# ButtonInputBoard.net
KiCad netlist of a schematic drawn in Altium Designer
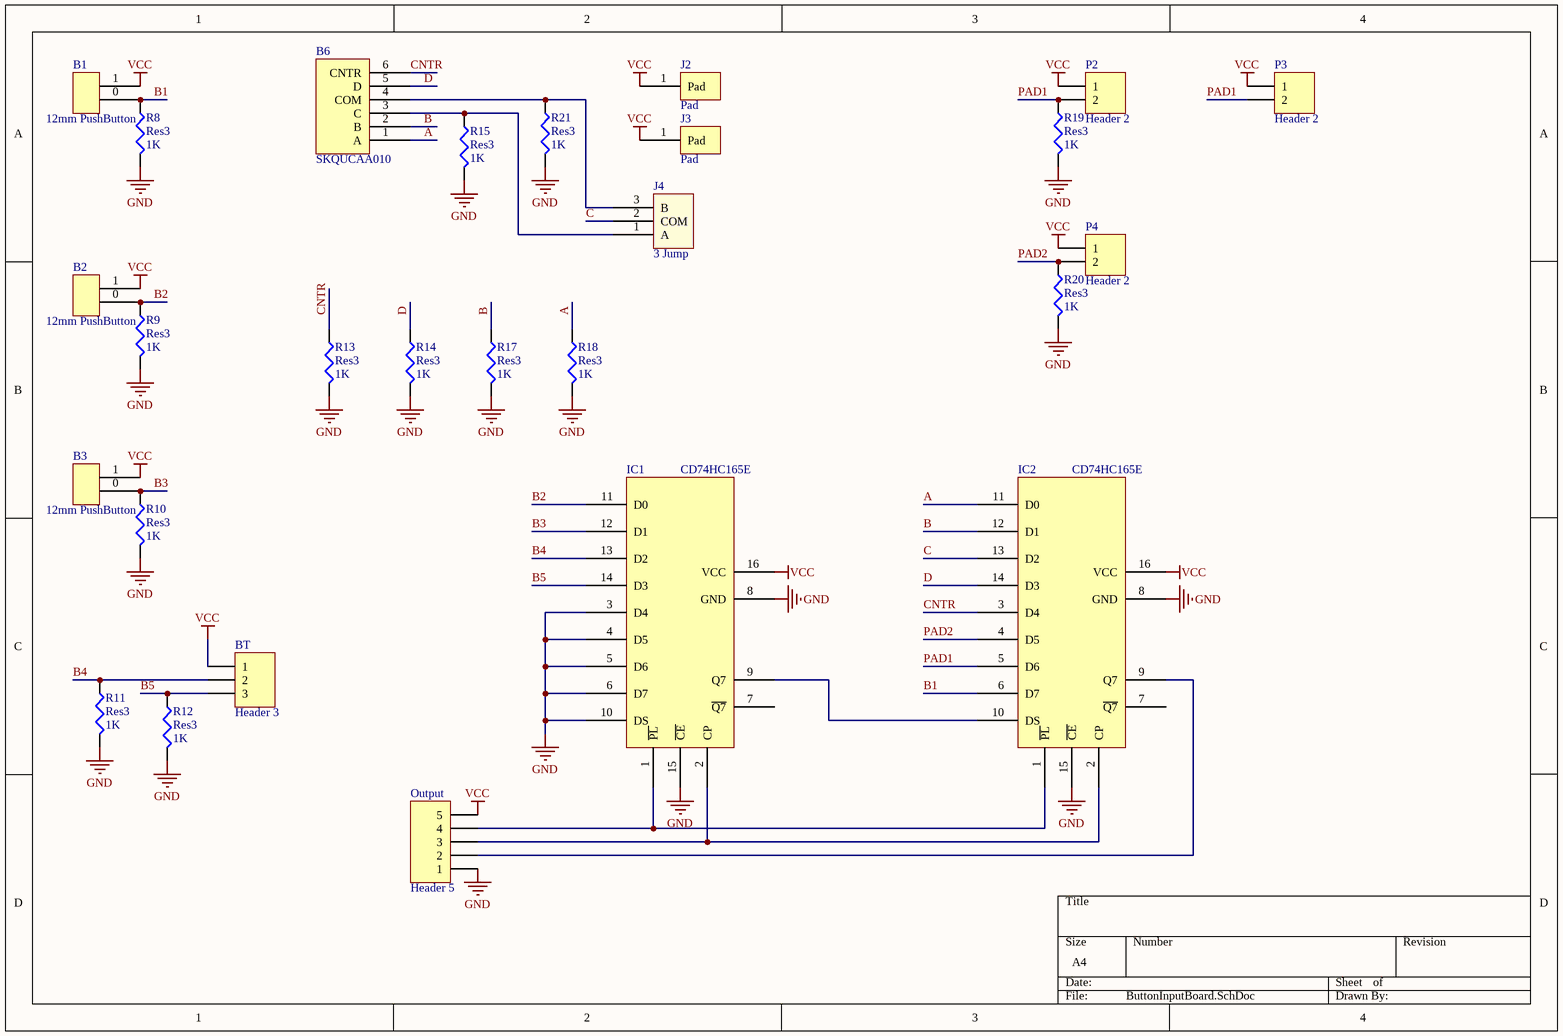
[diagram p0: ButtonInputBoard.SchDoc]

(export (version "E")
  (design (tool "Eeschema 10.0.6"))
  (components
    (comp (ref "B1")
      (value "12mm PushButton")
      (footprint "12mm PushButton")
      (libsource (lib "WheelLib") (part "12mm PushButton"))
    )
    (comp (ref "B2")
      (value "12mm PushButton")
      (footprint "12mm PushButton")
      (libsource (lib "WheelLib") (part "12mm PushButton"))
    )
    (comp (ref "B3")
      (value "12mm PushButton")
      (footprint "12mm PushButton")
      (libsource (lib "WheelLib") (part "12mm PushButton"))
    )
    (comp (ref "B6")
      (value "SKQUCAA010")
      (footprint "SKQUCAA010")
      (libsource (lib "WheelLib") (part "SKQUCAA010"))
    )
    (comp (ref "BT")
      (value "Header 3")
      (footprint "HDR1X3")
      (description "Header, 3-Pin")
      (fields (field (name "PUBLISHER") "Altium Limited"))
      (libsource (lib "Miscellaneous Connectors") (part "Header 3"))
    )
    (comp (ref "IC1")
      (value "CD74HC165E")
      (footprint "SD74HC165E")
      (description "8-Bit Shift Register")
      (libsource (lib "WheelLib") (part "CD74HC165E"))
    )
    (comp (ref "IC2")
      (value "CD74HC165E")
      (footprint "SD74HC165E")
      (description "8-Bit Shift Register")
      (libsource (lib "WheelLib") (part "CD74HC165E"))
    )
    (comp (ref "J2") (value "Pad") (footprint "Pad") (libsource (lib "WheelLib") (part "Pad")))
    (comp (ref "J3") (value "Pad") (footprint "Pad") (libsource (lib "WheelLib") (part "Pad")))
    (comp (ref "J4") (value "3 Jump") (footprint "3 Jump") (libsource (lib "WheelLib") (part "3 Jump")))
    (comp (ref "Output")
      (value "Header 5")
      (footprint "HDR1X5")
      (description "Header, 5-Pin")
      (fields (field (name "PUBLISHER") "Altium Limited"))
      (libsource (lib "Miscellaneous Connectors") (part "Header 5"))
    )
    (comp (ref "P2")
      (value "Header 2")
      (footprint "HDR1X2")
      (description "Header, 2-Pin")
      (fields (field (name "PUBLISHER") "Altium Limited"))
      (libsource (lib "Miscellaneous Connectors") (part "Header 2"))
    )
    (comp (ref "P3")
      (value "Header 2")
      (footprint "HDR1X2")
      (description "Header, 2-Pin")
      (fields (field (name "PUBLISHER") "Altium Limited"))
      (libsource (lib "Miscellaneous Connectors") (part "Header 2"))
    )
    (comp (ref "P4")
      (value "Header 2")
      (footprint "HDR1X2")
      (description "Header, 2-Pin")
      (fields (field (name "PUBLISHER") "Altium Limited"))
      (libsource (lib "Miscellaneous Connectors") (part "Header 2"))
    )
    (comp (ref "R8")
      (value "Res3")
      (footprint "J1-0603")
      (description "Resistor")
      (fields (field (name "ALTIUM_VALUE") "1K") (field (name "PUBLISHER") "Altium Limited"))
      (libsource (lib "Miscellaneous Devices") (part "Res3"))
    )
    (comp (ref "R9")
      (value "Res3")
      (footprint "J1-0603")
      (description "Resistor")
      (fields (field (name "ALTIUM_VALUE") "1K") (field (name "PUBLISHER") "Altium Limited"))
      (libsource (lib "Miscellaneous Devices") (part "Res3"))
    )
    (comp (ref "R10")
      (value "Res3")
      (footprint "J1-0603")
      (description "Resistor")
      (fields (field (name "ALTIUM_VALUE") "1K") (field (name "PUBLISHER") "Altium Limited"))
      (libsource (lib "Miscellaneous Devices") (part "Res3"))
    )
    (comp (ref "R11")
      (value "Res3")
      (footprint "J1-0603")
      (description "Resistor")
      (fields (field (name "ALTIUM_VALUE") "1K") (field (name "PUBLISHER") "Altium Limited"))
      (libsource (lib "Miscellaneous Devices") (part "Res3"))
    )
    (comp (ref "R12")
      (value "Res3")
      (footprint "J1-0603")
      (description "Resistor")
      (fields (field (name "ALTIUM_VALUE") "1K") (field (name "PUBLISHER") "Altium Limited"))
      (libsource (lib "Miscellaneous Devices") (part "Res3"))
    )
    (comp (ref "R13")
      (value "Res3")
      (footprint "J1-0603")
      (description "Resistor")
      (fields (field (name "ALTIUM_VALUE") "1K") (field (name "PUBLISHER") "Altium Limited"))
      (libsource (lib "Miscellaneous Devices") (part "Res3"))
    )
    (comp (ref "R14")
      (value "Res3")
      (footprint "J1-0603")
      (description "Resistor")
      (fields (field (name "ALTIUM_VALUE") "1K") (field (name "PUBLISHER") "Altium Limited"))
      (libsource (lib "Miscellaneous Devices") (part "Res3"))
    )
    (comp (ref "R15")
      (value "Res3")
      (footprint "J1-0603")
      (description "Resistor")
      (fields (field (name "ALTIUM_VALUE") "1K") (field (name "PUBLISHER") "Altium Limited"))
      (libsource (lib "Miscellaneous Devices") (part "Res3"))
    )
    (comp (ref "R17")
      (value "Res3")
      (footprint "J1-0603")
      (description "Resistor")
      (fields (field (name "ALTIUM_VALUE") "1K") (field (name "PUBLISHER") "Altium Limited"))
      (libsource (lib "Miscellaneous Devices") (part "Res3"))
    )
    (comp (ref "R18")
      (value "Res3")
      (footprint "J1-0603")
      (description "Resistor")
      (fields (field (name "ALTIUM_VALUE") "1K") (field (name "PUBLISHER") "Altium Limited"))
      (libsource (lib "Miscellaneous Devices") (part "Res3"))
    )
    (comp (ref "R19")
      (value "Res3")
      (footprint "J1-0603")
      (description "Resistor")
      (fields (field (name "ALTIUM_VALUE") "1K") (field (name "PUBLISHER") "Altium Limited"))
      (libsource (lib "Miscellaneous Devices") (part "Res3"))
    )
    (comp (ref "R20")
      (value "Res3")
      (footprint "J1-0603")
      (description "Resistor")
      (fields (field (name "ALTIUM_VALUE") "1K") (field (name "PUBLISHER") "Altium Limited"))
      (libsource (lib "Miscellaneous Devices") (part "Res3"))
    )
    (comp (ref "R21")
      (value "Res3")
      (footprint "J1-0603")
      (description "Resistor")
      (fields (field (name "ALTIUM_VALUE") "1K") (field (name "PUBLISHER") "Altium Limited"))
      (libsource (lib "Miscellaneous Devices") (part "Res3"))
    )
  )
  (nets
    (net (code "1") (name "/A") (class "Default")
      (node (ref "B6") (pin "1") (pinfunction "A_1") (pintype "passive"))
      (node (ref "IC2") (pin "11") (pinfunction "D0_11") (pintype "passive"))
      (node (ref "R18") (pin "1") (pinfunction "1_1") (pintype "passive"))
    )
    (net (code "2") (name "/B") (class "Default")
      (node (ref "B6") (pin "2") (pinfunction "B_2") (pintype "passive"))
      (node (ref "IC2") (pin "12") (pinfunction "D1_12") (pintype "passive"))
      (node (ref "R17") (pin "1") (pinfunction "1_1") (pintype "passive"))
    )
    (net (code "3") (name "/B1") (class "Default")
      (node (ref "B1") (pin "0") (pintype "passive"))
      (node (ref "IC2") (pin "6") (pinfunction "D7_6") (pintype "passive"))
      (node (ref "R8") (pin "1") (pinfunction "1_1") (pintype "passive"))
    )
    (net (code "4") (name "/B2") (class "Default")
      (node (ref "B2") (pin "0") (pintype "passive"))
      (node (ref "IC1") (pin "11") (pinfunction "D0_11") (pintype "passive"))
      (node (ref "R9") (pin "1") (pinfunction "1_1") (pintype "passive"))
    )
    (net (code "5") (name "/B3") (class "Default")
      (node (ref "B3") (pin "0") (pintype "passive"))
      (node (ref "IC1") (pin "12") (pinfunction "D1_12") (pintype "passive"))
      (node (ref "R10") (pin "1") (pinfunction "1_1") (pintype "passive"))
    )
    (net (code "6") (name "/B4") (class "Default")
      (node (ref "BT") (pin "2") (pinfunction "2_2") (pintype "passive"))
      (node (ref "IC1") (pin "13") (pinfunction "D2_13") (pintype "passive"))
      (node (ref "R11") (pin "1") (pinfunction "1_1") (pintype "passive"))
    )
    (net (code "7") (name "/B5") (class "Default")
      (node (ref "BT") (pin "3") (pinfunction "3_3") (pintype "passive"))
      (node (ref "IC1") (pin "14") (pinfunction "D3_14") (pintype "passive"))
      (node (ref "R12") (pin "1") (pinfunction "1_1") (pintype "passive"))
    )
    (net (code "8") (name "/C") (class "Default")
      (node (ref "IC2") (pin "13") (pinfunction "D2_13") (pintype "passive"))
      (node (ref "J4") (pin "2") (pinfunction "COM_2") (pintype "passive"))
    )
    (net (code "9") (name "/CNTR") (class "Default")
      (node (ref "B6") (pin "6") (pinfunction "CNTR_6") (pintype "passive"))
      (node (ref "IC2") (pin "3") (pinfunction "D4_3") (pintype "passive"))
      (node (ref "R13") (pin "1") (pinfunction "1_1") (pintype "passive"))
    )
    (net (code "10") (name "/D") (class "Default")
      (node (ref "B6") (pin "5") (pinfunction "D_5") (pintype "passive"))
      (node (ref "IC2") (pin "14") (pinfunction "D3_14") (pintype "passive"))
      (node (ref "R14") (pin "1") (pinfunction "1_1") (pintype "passive"))
    )
    (net (code "11") (name "/PAD1") (class "Default")
      (node (ref "IC2") (pin "5") (pinfunction "D6_5") (pintype "passive"))
      (node (ref "P2") (pin "2") (pinfunction "2_2") (pintype "passive"))
      (node (ref "P3") (pin "2") (pinfunction "2_2") (pintype "passive"))
      (node (ref "R19") (pin "1") (pinfunction "1_1") (pintype "passive"))
    )
    (net (code "12") (name "/PAD2") (class "Default")
      (node (ref "IC2") (pin "4") (pinfunction "D5_4") (pintype "passive"))
      (node (ref "P4") (pin "2") (pinfunction "2_2") (pintype "passive"))
      (node (ref "R20") (pin "1") (pinfunction "1_1") (pintype "passive"))
    )
    (net (code "13") (name "GND") (class "Default")
      (node (ref "IC1") (pin "10") (pinfunction "DS_10") (pintype "passive"))
      (node (ref "IC1") (pin "15") (pinfunction "~{CE}_15") (pintype "passive"))
      (node (ref "IC1") (pin "3") (pinfunction "D4_3") (pintype "passive"))
      (node (ref "IC1") (pin "4") (pinfunction "D5_4") (pintype "passive"))
      (node (ref "IC1") (pin "5") (pinfunction "D6_5") (pintype "passive"))
      (node (ref "IC1") (pin "6") (pinfunction "D7_6") (pintype "passive"))
      (node (ref "IC1") (pin "8") (pinfunction "GND_8") (pintype "power_in"))
      (node (ref "IC2") (pin "15") (pinfunction "~{CE}_15") (pintype "passive"))
      (node (ref "IC2") (pin "8") (pinfunction "GND_8") (pintype "power_in"))
      (node (ref "Output") (pin "1") (pinfunction "1_1") (pintype "passive"))
      (node (ref "R10") (pin "2") (pinfunction "2_2") (pintype "passive"))
      (node (ref "R11") (pin "2") (pinfunction "2_2") (pintype "passive"))
      (node (ref "R12") (pin "2") (pinfunction "2_2") (pintype "passive"))
      (node (ref "R13") (pin "2") (pinfunction "2_2") (pintype "passive"))
      (node (ref "R14") (pin "2") (pinfunction "2_2") (pintype "passive"))
      (node (ref "R15") (pin "2") (pinfunction "2_2") (pintype "passive"))
      (node (ref "R17") (pin "2") (pinfunction "2_2") (pintype "passive"))
      (node (ref "R18") (pin "2") (pinfunction "2_2") (pintype "passive"))
      (node (ref "R19") (pin "2") (pinfunction "2_2") (pintype "passive"))
      (node (ref "R20") (pin "2") (pinfunction "2_2") (pintype "passive"))
      (node (ref "R21") (pin "2") (pinfunction "2_2") (pintype "passive"))
      (node (ref "R8") (pin "2") (pinfunction "2_2") (pintype "passive"))
      (node (ref "R9") (pin "2") (pinfunction "2_2") (pintype "passive"))
    )
    (net (code "14") (name "Net-(B6-C)") (class "Default")
      (node (ref "B6") (pin "3") (pinfunction "C_3") (pintype "passive"))
      (node (ref "J4") (pin "1") (pinfunction "A_1") (pintype "passive"))
      (node (ref "R15") (pin "1") (pinfunction "1_1") (pintype "passive"))
    )
    (net (code "15") (name "Net-(B6-COM)") (class "Default")
      (node (ref "B6") (pin "4") (pinfunction "COM_4") (pintype "passive"))
      (node (ref "J4") (pin "3") (pinfunction "B_3") (pintype "passive"))
      (node (ref "R21") (pin "1") (pinfunction "1_1") (pintype "passive"))
    )
    (net (code "16") (name "Net-(IC1-CP)") (class "Default")
      (node (ref "IC1") (pin "2") (pinfunction "CP_2") (pintype "passive"))
      (node (ref "IC2") (pin "2") (pinfunction "CP_2") (pintype "passive"))
      (node (ref "Output") (pin "3") (pinfunction "3_3") (pintype "passive"))
    )
    (net (code "17") (name "Net-(IC1-Q7)") (class "Default")
      (node (ref "IC1") (pin "9") (pinfunction "Q7_9") (pintype "passive"))
      (node (ref "IC2") (pin "10") (pinfunction "DS_10") (pintype "passive"))
    )
    (net (code "18") (name "Net-(IC1-~{PL})") (class "Default")
      (node (ref "IC1") (pin "1") (pinfunction "~{PL}_1") (pintype "passive"))
      (node (ref "IC2") (pin "1") (pinfunction "~{PL}_1") (pintype "passive"))
      (node (ref "Output") (pin "4") (pinfunction "4_4") (pintype "passive"))
    )
    (net (code "19") (name "Net-(IC2-Q7)") (class "Default")
      (node (ref "IC2") (pin "9") (pinfunction "Q7_9") (pintype "passive"))
      (node (ref "Output") (pin "2") (pinfunction "2_2") (pintype "passive"))
    )
    (net (code "20") (name "VCC") (class "Default")
      (node (ref "B1") (pin "1") (pintype "passive"))
      (node (ref "B2") (pin "1") (pintype "passive"))
      (node (ref "B3") (pin "1") (pintype "passive"))
      (node (ref "BT") (pin "1") (pinfunction "1_1") (pintype "passive"))
      (node (ref "IC1") (pin "16") (pinfunction "VCC_16") (pintype "power_in"))
      (node (ref "IC2") (pin "16") (pinfunction "VCC_16") (pintype "power_in"))
      (node (ref "J2") (pin "1") (pinfunction "Pad_1") (pintype "passive"))
      (node (ref "J3") (pin "1") (pinfunction "Pad_1") (pintype "passive"))
      (node (ref "Output") (pin "5") (pinfunction "5_5") (pintype "passive"))
      (node (ref "P2") (pin "1") (pinfunction "1_1") (pintype "passive"))
      (node (ref "P3") (pin "1") (pinfunction "1_1") (pintype "passive"))
      (node (ref "P4") (pin "1") (pinfunction "1_1") (pintype "passive"))
    )
    (net (code "21") (name "unconnected-(IC1-~{Q7}-Pad7)") (class "Default")
      (node (ref "IC1") (pin "7") (pinfunction "~{Q7}_7") (pintype "passive"))
    )
    (net (code "22") (name "unconnected-(IC2-~{Q7}-Pad7)") (class "Default")
      (node (ref "IC2") (pin "7") (pinfunction "~{Q7}_7") (pintype "passive"))
    )
  )
)
